# Custom_MCU.net
KiCad netlist of a schematic drawn in Altium Designer
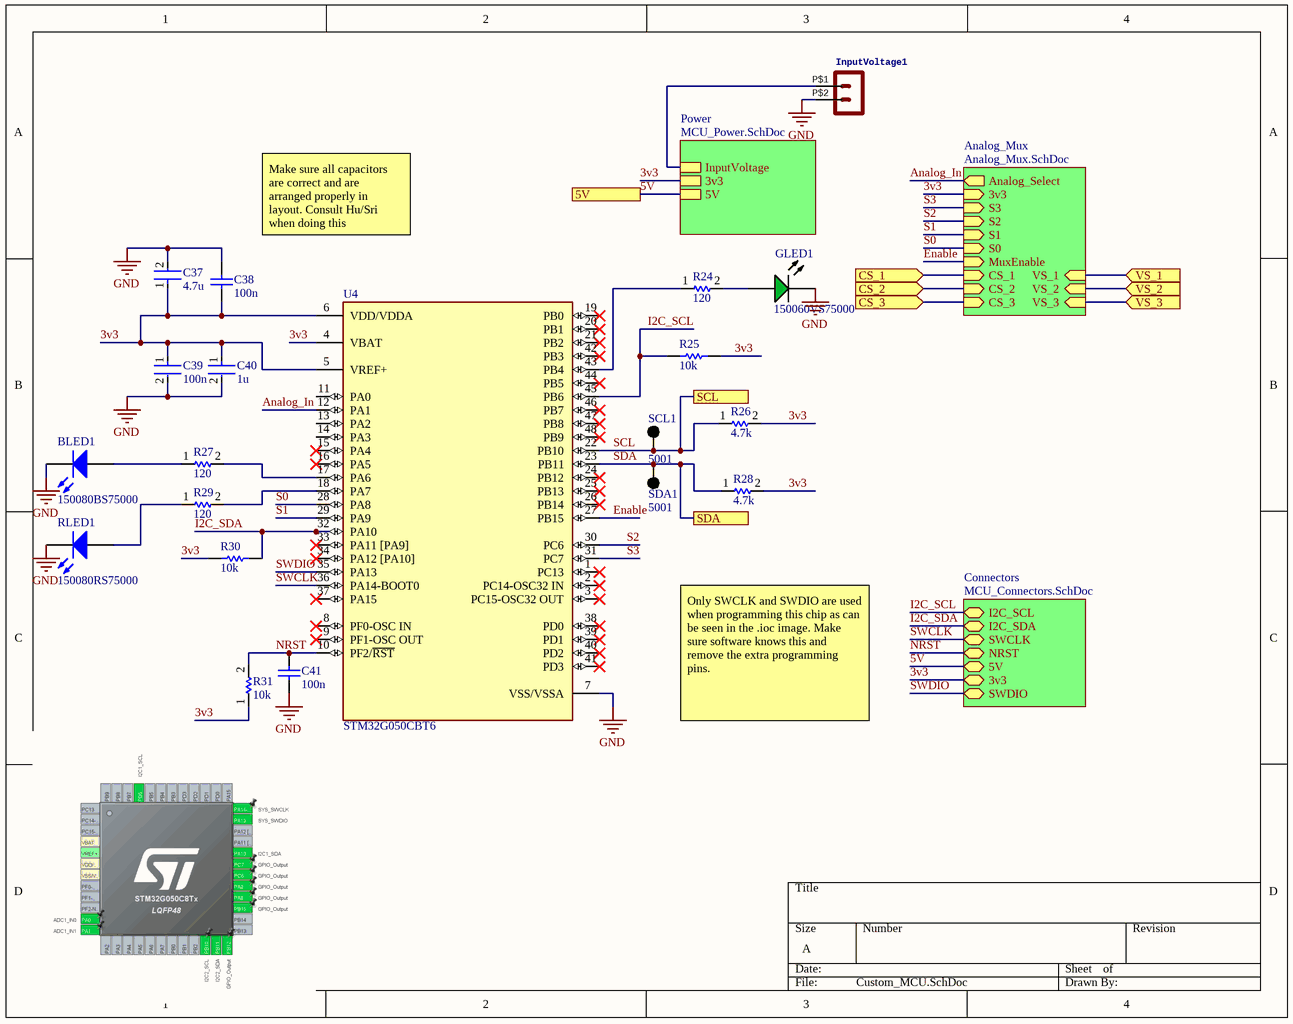
[diagram p0: Custom_MCU.SchDoc]

(export (version "E")
  (design (tool "Eeschema 10.0.6"))
  (components
    (comp (ref "BLED1")
      (value "150080BS75000")
      (footprint "0805_A")
      (description "SMD mono-color Chip LED, WL-SMCW, Blue")
      (fields (field (name "MANUFACTURER") "Wuerth Elektronik"))
      (libsource (lib "Altium Content Vault") (part "WE-LED_K1A2-2"))
    )
    (comp (ref "C37")
      (value "4.7u")
      (footprint "FP-CL282-IPC_C")
      (description "Cap Ceramic 4.7uF 10V X5R ±20% SMD 0402 +85°C Paper T/R")
      (fields (field (name "TOLERANCE") "20%") (field (name "JLCPCB PART NUMBER") "C23733"))
      (libsource (lib "Altium Content Vault") (part "b4654b650e69147ec39a6b967a45e02"))
    )
    (comp (ref "C38")
      (value "100n")
      (footprint "CAPC1050X55X23ML05T13")
      (description "Chip Capacitor, 100 nF, +/- 10%, 16 V, -55 to 125 degC, 0402 (1005 Metric), RoHS, Tape and Reel")
      (fields
        (field (name "MANUFACTURER") "Samsung Electro-Mechanics")
        (field (name "JLCPCB PART NUMBER") "C1525")
      )
      (libsource (lib "Altium Content Vault") (part "CAP-NP-2"))
    )
    (comp (ref "C39")
      (value "100n")
      (footprint "FP-CL10-0_1-MFG")
      (description "CAP CER 0.1UF 50V X7R 0603")
      (fields
        (field (name "MANUFACTURER") "Samsung Electro-Mechanics America, Inc")
        (field (name "MANUFACTURER PART NUMBER") "CL10B104JB8NNNC")
      )
      (libsource (lib "Altium Content Vault") (part "b4654b650e69147ec39a6b967a45e02"))
    )
    (comp (ref "C40")
      (value "1u")
      (footprint "FP-CL542-IPC_C")
      (description "Cap Ceramic 1uF 25V X5R ±10% SMD 0402 +85°C Paper T/R")
      (fields (field (name "TOLERANCE") "10%") (field (name "JLCPCB PART NUMBER") "C52923"))
      (libsource (lib "Altium Content Vault") (part "b4654b650e69147ec39a6b967a45e02"))
    )
    (comp (ref "C41")
      (value "100n")
      (footprint "CAPC1050X55X23ML05T13")
      (description "Chip Capacitor, 100 nF, +/- 10%, 16 V, -55 to 125 degC, 0402 (1005 Metric), RoHS, Tape and Reel")
      (fields
        (field (name "MANUFACTURER") "Samsung Electro-Mechanics")
        (field (name "JLCPCB PART NUMBER") "C1525")
      )
      (libsource (lib "Altium Content Vault") (part "CAP-NP-2"))
    )
    (comp (ref "GLED1")
      (value "150060VS75000")
      (footprint "WE-150060VS75000_V")
      (libsource (lib "Altium Content Vault") (part "LED_GREEN_K1A2-2"))
    )
    (comp (ref "InputVoltage1")
      (value "Molex - Micro-Fit 3.0 Series connector,  3.00mm (0.118\") pitch header, 2 positions.")
      (footprint "44914-0201")
      (libsource (lib "Molex Microfit") (part "HEADER_POS2_?44914-0201"))
    )
    (comp (ref "R24")
      (value "120")
      (footprint "0402WGF1200TCE")
      (description "±1% 1/16W ±100ppm/℃ 120Ω 0402 Chip Resistor - Surface Mount ROHS")
      (fields
        (field (name "MANUFACTURER") "UNI-ROYAL")
        (field (name "MANUFACTURER PART NUMBER") "0402WGF1200TCE")
      )
      (libsource (lib "RoverResistors") (part "0402WGF1200TCE"))
    )
    (comp (ref "R25")
      (value "10k")
      (footprint "RESC1609X55X30LL15T15")
      (description "Chip Resistor, 10 KOhm, +/- 1%, 0.1 W, -55 to 155 degC, 0603 (1608 Metric), RoHS, Tape and Reel")
      (fields (field (name "TOLERANCE") "1%") (field (name "MANUFACTURER") "Panasonic"))
      (libsource (lib "Altium Content Vault") (part "RES-2"))
    )
    (comp (ref "R26")
      (value "4.7k")
      (footprint "0402WGF4701TCE")
      (description "1/16W ±1% 4.7kΩ ±100ppm/℃ 0402 Chip Resistor - Surface Mount ROHS")
      (fields
        (field (name "MANUFACTURER") "UNI-ROYAL")
        (field (name "MANUFACTURER PART NUMBER") "0402WGF4701TCE")
      )
      (libsource (lib "RoverResistors") (part "0402WGF4701TCE"))
    )
    (comp (ref "R27")
      (value "120")
      (footprint "0402WGF1200TCE")
      (description "±1% 1/16W ±100ppm/℃ 120Ω 0402 Chip Resistor - Surface Mount ROHS")
      (fields
        (field (name "MANUFACTURER") "UNI-ROYAL")
        (field (name "MANUFACTURER PART NUMBER") "0402WGF1200TCE")
      )
      (libsource (lib "RoverResistors") (part "0402WGF1200TCE"))
    )
    (comp (ref "R28")
      (value "4.7k")
      (footprint "0402WGF4701TCE")
      (description "1/16W ±1% 4.7kΩ ±100ppm/℃ 0402 Chip Resistor - Surface Mount ROHS")
      (fields
        (field (name "MANUFACTURER") "UNI-ROYAL")
        (field (name "MANUFACTURER PART NUMBER") "0402WGF4701TCE")
      )
      (libsource (lib "RoverResistors") (part "0402WGF4701TCE"))
    )
    (comp (ref "R29")
      (value "120")
      (footprint "0402WGF1200TCE")
      (description "±1% 1/16W ±100ppm/℃ 120Ω 0402 Chip Resistor - Surface Mount ROHS")
      (fields
        (field (name "MANUFACTURER") "UNI-ROYAL")
        (field (name "MANUFACTURER PART NUMBER") "0402WGF1200TCE")
      )
      (libsource (lib "RoverResistors") (part "0402WGF1200TCE"))
    )
    (comp (ref "R30")
      (value "10k")
      (footprint "RESC1609X55X30LL15T15")
      (description "Chip Resistor, 10 KOhm, +/- 1%, 0.1 W, -55 to 155 degC, 0603 (1608 Metric), RoHS, Tape and Reel")
      (fields (field (name "TOLERANCE") "1%") (field (name "MANUFACTURER") "Panasonic"))
      (libsource (lib "Altium Content Vault") (part "RES-2"))
    )
    (comp (ref "R31")
      (value "10k")
      (footprint "0402WGF1002TCE")
      (description "1/16W ±1% ±100ppm/℃ 10kΩ 0402 Chip Resistor - Surface Mount ROHS")
      (fields
        (field (name "MANUFACTURER") "UNI-ROYAL")
        (field (name "MANUFACTURER PART NUMBER") "0402WGF1002TCE")
      )
      (libsource (lib "RoverResistors") (part "0402WGF1002TCE"))
    )
    (comp (ref "RLED1")
      (value "150080RS75000")
      (footprint "0805_A")
      (description "SMD mono-color Chip LED, WL-SMCW, Red")
      (fields (field (name "MANUFACTURER") "Wuerth Elektronik"))
      (libsource (lib "Altium Content Vault") (part "WE-LED_K1A2-2"))
    )
    (comp (ref "SCL1")
      (value "5001")
      (footprint "KSTN-5001")
      (description "Test Point, Black, 1-Pin THD, RoHS, Bulk")
      (fields (field (name "MANUFACTURER") "Keystone"))
      (libsource (lib "Altium Content Vault") (part "KSTN-TP-5001"))
    )
    (comp (ref "SDA1")
      (value "5001")
      (footprint "KSTN-5001")
      (description "Test Point, Black, 1-Pin THD, RoHS, Bulk")
      (fields (field (name "MANUFACTURER") "Keystone"))
      (libsource (lib "Altium Content Vault") (part "KSTN-TP-5001"))
    )
    (comp (ref "U4")
      (value "STM32G050CBT6")
      (footprint "FP-LQFP48-5B-MFG")
      (description "IC MCU 32BIT 128KB FLASH 48LQFP")
      (fields
        (field (name "OCTOPART") "https://octopart.com/stm32g071cbt6-stmicroelectronics-96627027")
        (field (name "MANUFACTURER") "STMicroelectronics")
      )
      (libsource (lib "Altium Content Vault") (part "c9f63a35dbd129b66bfedb266152198"))
    )
  )
  (nets
    (net (code "1") (name "/3v3") (class "Default")
      (node (ref "C37") (pin "1") (pinfunction "1_1") (pintype "passive"))
      (node (ref "C38") (pin "2") (pinfunction "2_2") (pintype "passive"))
      (node (ref "C39") (pin "1") (pinfunction "1_1") (pintype "passive"))
      (node (ref "C40") (pin "1") (pinfunction "1_1") (pintype "passive"))
      (node (ref "R25") (pin "1") (pinfunction "1_1") (pintype "passive"))
      (node (ref "R26") (pin "2") (pinfunction "2_2") (pintype "passive"))
      (node (ref "R28") (pin "2") (pinfunction "2_2") (pintype "passive"))
      (node (ref "R30") (pin "1") (pinfunction "1_1") (pintype "passive"))
      (node (ref "R31") (pin "1") (pinfunction "1_1") (pintype "passive"))
      (node (ref "U4") (pin "4") (pinfunction "VBAT_4") (pintype "power_in"))
      (node (ref "U4") (pin "5") (pinfunction "VREF+_5") (pintype "power_in"))
      (node (ref "U4") (pin "6") (pinfunction "VDD/VDDA_6") (pintype "power_in"))
    )
    (net (code "3") (name "/Analog_In") (class "Default")
      (node (ref "U4") (pin "12") (pinfunction "PA1_12") (pintype "bidirectional"))
    )
    (net (code "7") (name "/Enable") (class "Default")
      (node (ref "U4") (pin "27") (pinfunction "PB15_27") (pintype "bidirectional"))
    )
    (net (code "8") (name "/I2C_SCL") (class "Default")
      (node (ref "R25") (pin "2") (pinfunction "2_2") (pintype "passive"))
      (node (ref "U4") (pin "45") (pinfunction "PB6_45") (pintype "bidirectional"))
    )
    (net (code "9") (name "/I2C_SDA") (class "Default")
      (node (ref "R30") (pin "2") (pinfunction "2_2") (pintype "passive"))
      (node (ref "U4") (pin "32") (pinfunction "PA10_32") (pintype "bidirectional"))
    )
    (net (code "10") (name "/InputVoltage") (class "Default")
      (node (ref "InputVoltage1") (pin "P$1") (pinfunction "1_P$1") (pintype "passive"))
    )
    (net (code "11") (name "/NRST") (class "Default")
      (node (ref "C41") (pin "2") (pinfunction "2_2") (pintype "passive"))
      (node (ref "R31") (pin "2") (pinfunction "2_2") (pintype "passive"))
      (node (ref "U4") (pin "10") (pinfunction "PF2/~{RST}_10") (pintype "bidirectional"))
    )
    (net (code "12") (name "/S0") (class "Default")
      (node (ref "U4") (pin "28") (pinfunction "PA8_28") (pintype "bidirectional"))
    )
    (net (code "13") (name "/S1") (class "Default")
      (node (ref "U4") (pin "29") (pinfunction "PA9_29") (pintype "bidirectional"))
    )
    (net (code "14") (name "/S2") (class "Default")
      (node (ref "U4") (pin "30") (pinfunction "PC6_30") (pintype "bidirectional"))
    )
    (net (code "15") (name "/S3") (class "Default")
      (node (ref "U4") (pin "31") (pinfunction "PC7_31") (pintype "bidirectional"))
    )
    (net (code "16") (name "/SCL") (class "Default")
      (node (ref "R26") (pin "1") (pinfunction "1_1") (pintype "passive"))
      (node (ref "SCL1") (pin "1") (pintype "passive"))
      (node (ref "U4") (pin "22") (pinfunction "PB10_22") (pintype "bidirectional"))
    )
    (net (code "17") (name "/SDA") (class "Default")
      (node (ref "R28") (pin "1") (pinfunction "1_1") (pintype "passive"))
      (node (ref "SDA1") (pin "1") (pintype "passive"))
      (node (ref "U4") (pin "23") (pinfunction "PB11_23") (pintype "bidirectional"))
    )
    (net (code "18") (name "/SWCLK") (class "Default")
      (node (ref "U4") (pin "36") (pinfunction "PA14-BOOT0_36") (pintype "bidirectional"))
    )
    (net (code "19") (name "/SWDIO") (class "Default")
      (node (ref "U4") (pin "35") (pinfunction "PA13_35") (pintype "bidirectional"))
    )
    (net (code "23") (name "GND") (class "Default")
      (node (ref "BLED1") (pin "1") (pinfunction "K_1") (pintype "passive"))
      (node (ref "C37") (pin "2") (pinfunction "2_2") (pintype "passive"))
      (node (ref "C38") (pin "1") (pinfunction "1_1") (pintype "passive"))
      (node (ref "C39") (pin "2") (pinfunction "2_2") (pintype "passive"))
      (node (ref "C40") (pin "2") (pinfunction "2_2") (pintype "passive"))
      (node (ref "C41") (pin "1") (pinfunction "1_1") (pintype "passive"))
      (node (ref "GLED1") (pin "1") (pinfunction "K_1") (pintype "passive"))
      (node (ref "InputVoltage1") (pin "P$2") (pinfunction "2_P$2") (pintype "passive"))
      (node (ref "RLED1") (pin "1") (pinfunction "K_1") (pintype "passive"))
      (node (ref "U4") (pin "7") (pinfunction "VSS/VSSA_7") (pintype "power_in"))
    )
    (net (code "24") (name "Net-(BLED1-A)") (class "Default")
      (node (ref "BLED1") (pin "2") (pinfunction "A_2") (pintype "passive"))
      (node (ref "R27") (pin "1") (pinfunction "1_1") (pintype "passive"))
    )
    (net (code "25") (name "Net-(GLED1-A)") (class "Default")
      (node (ref "GLED1") (pin "2") (pinfunction "A_2") (pintype "passive"))
      (node (ref "R24") (pin "2") (pinfunction "2_2") (pintype "passive"))
    )
    (net (code "26") (name "Net-(RLED1-A)") (class "Default")
      (node (ref "R29") (pin "1") (pinfunction "1_1") (pintype "passive"))
      (node (ref "RLED1") (pin "2") (pinfunction "A_2") (pintype "passive"))
    )
    (net (code "27") (name "Net-(U4-PA6)") (class "Default")
      (node (ref "R27") (pin "2") (pinfunction "2_2") (pintype "passive"))
      (node (ref "U4") (pin "17") (pinfunction "PA6_17") (pintype "bidirectional"))
    )
    (net (code "28") (name "Net-(U4-PA7)") (class "Default")
      (node (ref "R29") (pin "2") (pinfunction "2_2") (pintype "passive"))
      (node (ref "U4") (pin "18") (pinfunction "PA7_18") (pintype "bidirectional"))
    )
    (net (code "29") (name "Net-(U4-PB4)") (class "Default")
      (node (ref "R24") (pin "1") (pinfunction "1_1") (pintype "passive"))
      (node (ref "U4") (pin "43") (pinfunction "PB4_43") (pintype "bidirectional"))
    )
    (net (code "30") (name "unconnected-(U4-PA0-Pad11)") (class "Default")
      (node (ref "U4") (pin "11") (pinfunction "PA0_11") (pintype "bidirectional"))
    )
    (net (code "31") (name "unconnected-(U4-PA2-Pad13)") (class "Default")
      (node (ref "U4") (pin "13") (pinfunction "PA2_13") (pintype "bidirectional"))
    )
    (net (code "32") (name "unconnected-(U4-PA3-Pad14)") (class "Default")
      (node (ref "U4") (pin "14") (pinfunction "PA3_14") (pintype "bidirectional"))
    )
    (net (code "33") (name "unconnected-(U4-PA4-Pad15)") (class "Default")
      (node (ref "U4") (pin "15") (pinfunction "PA4_15") (pintype "bidirectional+no_connect"))
    )
    (net (code "34") (name "unconnected-(U4-PA5-Pad16)") (class "Default")
      (node (ref "U4") (pin "16") (pinfunction "PA5_16") (pintype "bidirectional+no_connect"))
    )
    (net (code "35") (name "unconnected-(U4-PA11_[PA9]-Pad33)") (class "Default")
      (node (ref "U4") (pin "33") (pinfunction "PA11_[PA9]_33") (pintype "bidirectional+no_connect"))
    )
    (net (code "36") (name "unconnected-(U4-PA12_[PA10]-Pad34)") (class "Default")
      (node (ref "U4") (pin "34") (pinfunction "PA12_[PA10]_34") (pintype "bidirectional+no_connect"))
    )
    (net (code "37") (name "unconnected-(U4-PA15-Pad37)") (class "Default")
      (node (ref "U4") (pin "37") (pinfunction "PA15_37") (pintype "bidirectional+no_connect"))
    )
    (net (code "38") (name "unconnected-(U4-PB0-Pad19)") (class "Default")
      (node (ref "U4") (pin "19") (pinfunction "PB0_19") (pintype "bidirectional+no_connect"))
    )
    (net (code "39") (name "unconnected-(U4-PB1-Pad20)") (class "Default")
      (node (ref "U4") (pin "20") (pinfunction "PB1_20") (pintype "bidirectional+no_connect"))
    )
    (net (code "40") (name "unconnected-(U4-PB2-Pad21)") (class "Default")
      (node (ref "U4") (pin "21") (pinfunction "PB2_21") (pintype "bidirectional+no_connect"))
    )
    (net (code "41") (name "unconnected-(U4-PB3-Pad42)") (class "Default")
      (node (ref "U4") (pin "42") (pinfunction "PB3_42") (pintype "bidirectional+no_connect"))
    )
    (net (code "42") (name "unconnected-(U4-PB5-Pad44)") (class "Default")
      (node (ref "U4") (pin "44") (pinfunction "PB5_44") (pintype "bidirectional+no_connect"))
    )
    (net (code "43") (name "unconnected-(U4-PB7-Pad46)") (class "Default")
      (node (ref "U4") (pin "46") (pinfunction "PB7_46") (pintype "bidirectional+no_connect"))
    )
    (net (code "44") (name "unconnected-(U4-PB8-Pad47)") (class "Default")
      (node (ref "U4") (pin "47") (pinfunction "PB8_47") (pintype "bidirectional+no_connect"))
    )
    (net (code "45") (name "unconnected-(U4-PB9-Pad48)") (class "Default")
      (node (ref "U4") (pin "48") (pinfunction "PB9_48") (pintype "bidirectional+no_connect"))
    )
    (net (code "46") (name "unconnected-(U4-PB12-Pad24)") (class "Default")
      (node (ref "U4") (pin "24") (pinfunction "PB12_24") (pintype "bidirectional+no_connect"))
    )
    (net (code "47") (name "unconnected-(U4-PB13-Pad25)") (class "Default")
      (node (ref "U4") (pin "25") (pinfunction "PB13_25") (pintype "bidirectional+no_connect"))
    )
    (net (code "48") (name "unconnected-(U4-PB14-Pad26)") (class "Default")
      (node (ref "U4") (pin "26") (pinfunction "PB14_26") (pintype "bidirectional+no_connect"))
    )
    (net (code "49") (name "unconnected-(U4-PC13-Pad1)") (class "Default")
      (node (ref "U4") (pin "1") (pinfunction "PC13_1") (pintype "bidirectional+no_connect"))
    )
    (net (code "50") (name "unconnected-(U4-PC14-OSC32_IN-Pad2)") (class "Default")
      (node (ref "U4") (pin "2") (pinfunction "PC14-OSC32_IN_2") (pintype "bidirectional+no_connect"))
    )
    (net (code "51") (name "unconnected-(U4-PC15-OSC32_OUT-Pad3)") (class "Default")
      (node (ref "U4") (pin "3") (pinfunction "PC15-OSC32_OUT_3") (pintype "bidirectional+no_connect"))
    )
    (net (code "52") (name "unconnected-(U4-PD0-Pad38)") (class "Default")
      (node (ref "U4") (pin "38") (pinfunction "PD0_38") (pintype "bidirectional+no_connect"))
    )
    (net (code "53") (name "unconnected-(U4-PD1-Pad39)") (class "Default")
      (node (ref "U4") (pin "39") (pinfunction "PD1_39") (pintype "bidirectional+no_connect"))
    )
    (net (code "54") (name "unconnected-(U4-PD2-Pad40)") (class "Default")
      (node (ref "U4") (pin "40") (pinfunction "PD2_40") (pintype "bidirectional+no_connect"))
    )
    (net (code "55") (name "unconnected-(U4-PD3-Pad41)") (class "Default")
      (node (ref "U4") (pin "41") (pinfunction "PD3_41") (pintype "bidirectional+no_connect"))
    )
    (net (code "56") (name "unconnected-(U4-PF0-OSC_IN-Pad8)") (class "Default")
      (node (ref "U4") (pin "8") (pinfunction "PF0-OSC_IN_8") (pintype "bidirectional+no_connect"))
    )
    (net (code "57") (name "unconnected-(U4-PF1-OSC_OUT-Pad9)") (class "Default")
      (node (ref "U4") (pin "9") (pinfunction "PF1-OSC_OUT_9") (pintype "bidirectional+no_connect"))
    )
  )
)
